# untitled.net
KiCad netlist of a schematic drawn in EAGLE
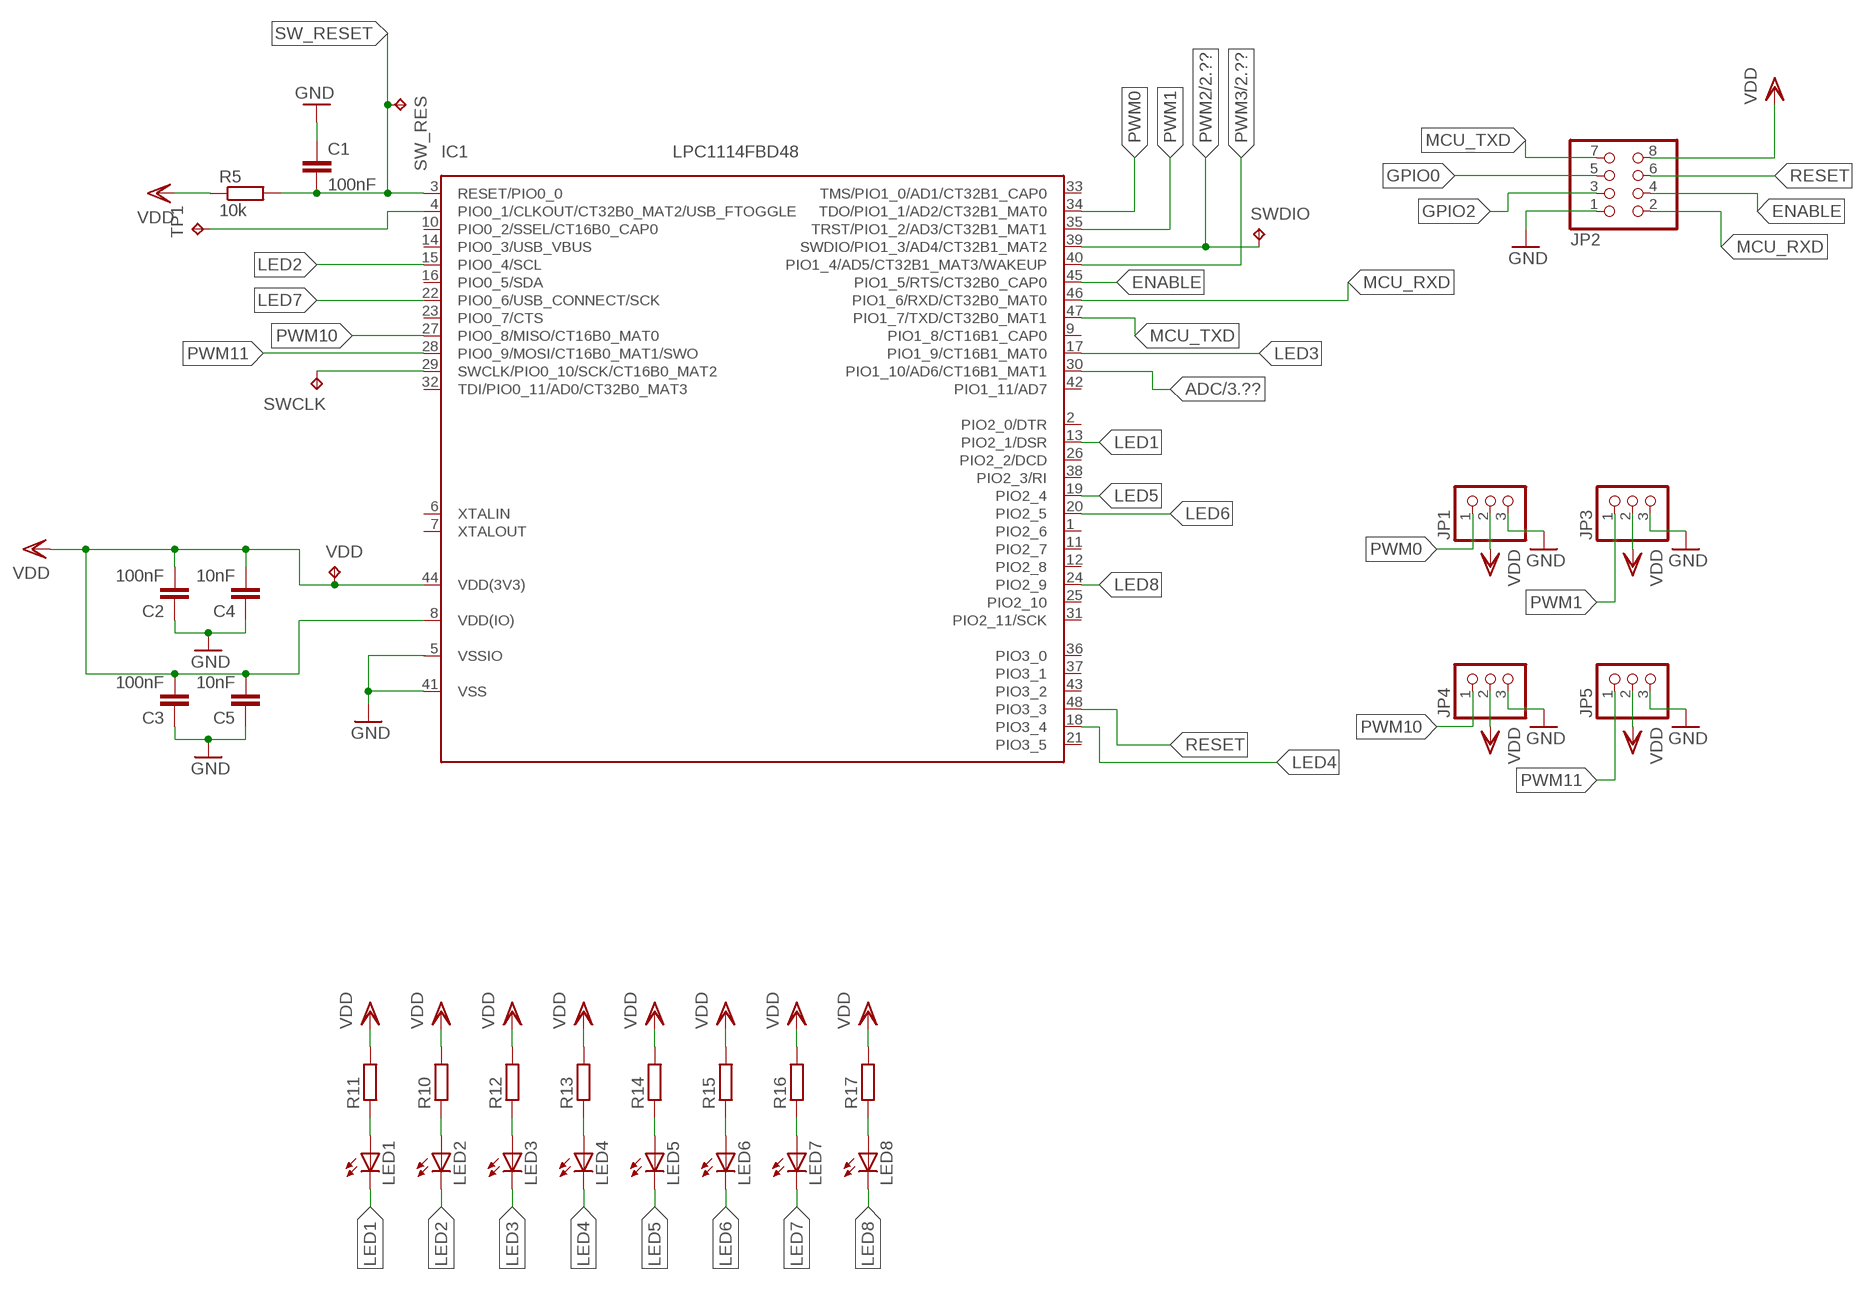
[diagram p0: schematic, sheet 1]
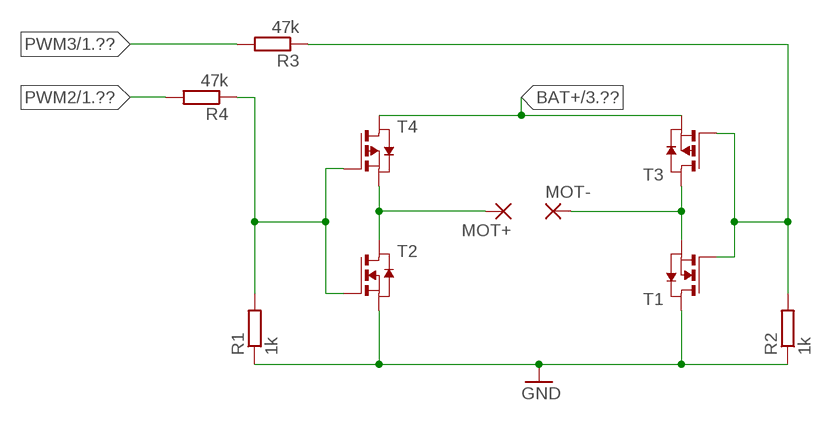
[diagram p1: schematic, sheet 2]
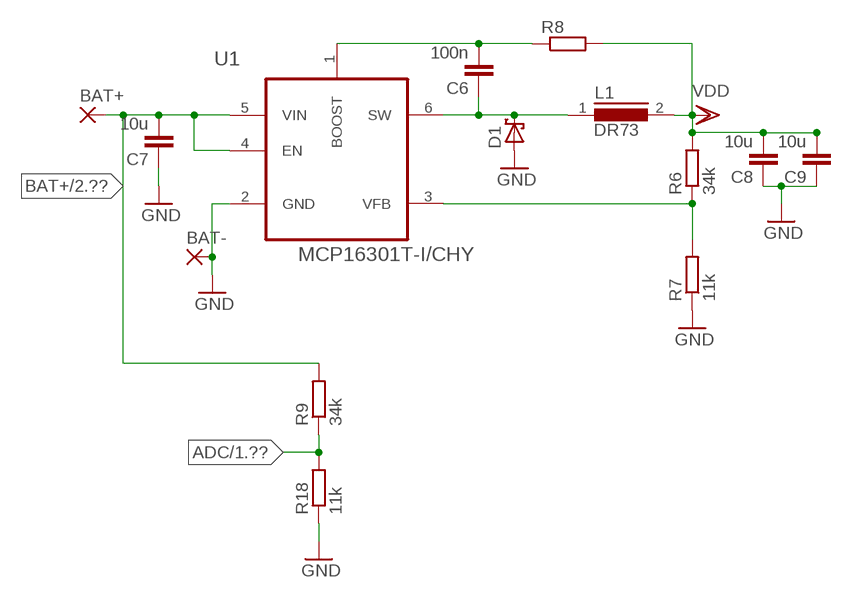
[diagram p2: schematic, sheet 3]

(export (version "E")
  (design (tool "Eeschema 10.0.6"))
  (components
    (comp (ref "MOT+")
      (value "SMD5")
      (footprint "eagle-import:SMD2,54-5,08")
      (libsource (lib "eagle-import") (part "SMD5"))
    )
    (comp (ref "MOT-")
      (value "SMD5")
      (footprint "eagle-import:SMD2,54-5,08")
      (libsource (lib "eagle-import") (part "SMD5"))
    )
    (comp (ref "R1")
      (value "1k")
      (footprint "eagle-import:R0805")
      (libsource (lib "eagle-import") (part "R-EU_R0805"))
    )
    (comp (ref "R2")
      (value "1k")
      (footprint "eagle-import:R0805")
      (libsource (lib "eagle-import") (part "R-EU_R0805"))
    )
    (comp (ref "R3")
      (value "47k")
      (footprint "eagle-import:R0805")
      (libsource (lib "eagle-import") (part "R-EU_R0805"))
    )
    (comp (ref "R4")
      (value "47k")
      (footprint "eagle-import:R0805")
      (libsource (lib "eagle-import") (part "R-EU_R0805"))
    )
    (comp (ref "T1")
      (value "NMOSSOT23")
      (footprint "eagle-import:SOT-23")
      (libsource (lib "eagle-import") (part "NMOSSOT23"))
    )
    (comp (ref "T2")
      (value "NMOSSOT23")
      (footprint "eagle-import:SOT-23")
      (libsource (lib "eagle-import") (part "NMOSSOT23"))
    )
    (comp (ref "T3")
      (value "PMOSSOT23")
      (footprint "eagle-import:SOT-23")
      (libsource (lib "eagle-import") (part "PMOSSOT23"))
    )
    (comp (ref "T4")
      (value "PMOSSOT23")
      (footprint "eagle-import:SOT-23")
      (libsource (lib "eagle-import") (part "PMOSSOT23"))
    )
    (comp (ref "BAT+")
      (value "SMD5")
      (footprint "eagle-import:SMD2,54-5,08")
      (libsource (lib "eagle-import") (part "SMD5"))
    )
    (comp (ref "BAT-")
      (value "SMD5")
      (footprint "eagle-import:SMD2,54-5,08")
      (libsource (lib "eagle-import") (part "SMD5"))
    )
    (comp (ref "C6")
      (value "100n")
      (footprint "eagle-import:C0805")
      (libsource (lib "eagle-import") (part "C-EUC0805"))
    )
    (comp (ref "C7")
      (value "10u")
      (footprint "eagle-import:C0805")
      (libsource (lib "eagle-import") (part "C-EUC0805"))
    )
    (comp (ref "C8")
      (value "10u")
      (footprint "eagle-import:C0805")
      (libsource (lib "eagle-import") (part "C-EUC0805"))
    )
    (comp (ref "C9")
      (value "10u")
      (footprint "eagle-import:C0805")
      (libsource (lib "eagle-import") (part "C-EUC0805"))
    )
    (comp (ref "D1")
      (value "SCHOTTKY-DIODESMD")
      (footprint "eagle-import:SMB")
      (libsource (lib "eagle-import") (part "SCHOTTKY-DIODESMD"))
    )
    (comp (ref "L1")
      (value "DR73")
      (footprint "eagle-import:DR73")
      (libsource (lib "eagle-import") (part "DR73"))
    )
    (comp (ref "R6")
      (value "34k")
      (footprint "eagle-import:R0805")
      (libsource (lib "eagle-import") (part "R-EU_R0805"))
    )
    (comp (ref "R7")
      (value "11k")
      (footprint "eagle-import:R0805")
      (libsource (lib "eagle-import") (part "R-EU_R0805"))
    )
    (comp (ref "R8")
      (value "R-EU_R0603")
      (footprint "eagle-import:R0603")
      (libsource (lib "eagle-import") (part "R-EU_R0603"))
    )
    (comp (ref "R9")
      (value "34k")
      (footprint "eagle-import:R0805")
      (libsource (lib "eagle-import") (part "R-EU_R0805"))
    )
    (comp (ref "R18")
      (value "11k")
      (footprint "eagle-import:R0805")
      (libsource (lib "eagle-import") (part "R-EU_R0805"))
    )
    (comp (ref "U1")
      (value "MCP16301T-I/CHY")
      (footprint "eagle-import:SOT95P290X145-6N")
      (libsource (lib "eagle-import") (part "MCP16301T-I/CHY"))
    )
    (comp (ref "C1")
      (value "100nF")
      (footprint "eagle-import:C0805")
      (libsource (lib "eagle-import") (part "C-EUC0805"))
    )
    (comp (ref "C2")
      (value "100nF")
      (footprint "eagle-import:C0805")
      (libsource (lib "eagle-import") (part "C-EUC0805"))
    )
    (comp (ref "C3")
      (value "100nF")
      (footprint "eagle-import:C0805")
      (libsource (lib "eagle-import") (part "C-EUC0805"))
    )
    (comp (ref "C4")
      (value "10nF")
      (footprint "eagle-import:C0805")
      (libsource (lib "eagle-import") (part "C-EUC0805"))
    )
    (comp (ref "C5")
      (value "10nF")
      (footprint "eagle-import:C0805")
      (libsource (lib "eagle-import") (part "C-EUC0805"))
    )
    (comp (ref "IC1")
      (value "LPC1114FBD48")
      (footprint "eagle-import:LQFP48-7X7")
      (libsource (lib "eagle-import") (part "LPC1114FBD48"))
    )
    (comp (ref "JP1")
      (value "PINHD-1X3")
      (footprint "eagle-import:1X03")
      (libsource (lib "eagle-import") (part "PINHD-1X3"))
    )
    (comp (ref "JP2")
      (value "PINHD-2X4")
      (footprint "eagle-import:2X04")
      (libsource (lib "eagle-import") (part "PINHD-2X4"))
    )
    (comp (ref "JP3")
      (value "PINHD-1X3")
      (footprint "eagle-import:1X03")
      (libsource (lib "eagle-import") (part "PINHD-1X3"))
    )
    (comp (ref "JP4")
      (value "PINHD-1X3")
      (footprint "eagle-import:1X03")
      (libsource (lib "eagle-import") (part "PINHD-1X3"))
    )
    (comp (ref "JP5")
      (value "PINHD-1X3")
      (footprint "eagle-import:1X03")
      (libsource (lib "eagle-import") (part "PINHD-1X3"))
    )
    (comp (ref "LED1")
      (value "LEDCHIP-LED0805")
      (footprint "eagle-import:CHIP-LED0805")
      (libsource (lib "eagle-import") (part "LEDCHIP-LED0805"))
    )
    (comp (ref "LED2")
      (value "LEDCHIP-LED0805")
      (footprint "eagle-import:CHIP-LED0805")
      (libsource (lib "eagle-import") (part "LEDCHIP-LED0805"))
    )
    (comp (ref "LED3")
      (value "LEDCHIP-LED0805")
      (footprint "eagle-import:CHIP-LED0805")
      (libsource (lib "eagle-import") (part "LEDCHIP-LED0805"))
    )
    (comp (ref "LED4")
      (value "LEDCHIP-LED0805")
      (footprint "eagle-import:CHIP-LED0805")
      (libsource (lib "eagle-import") (part "LEDCHIP-LED0805"))
    )
    (comp (ref "LED5")
      (value "LEDCHIP-LED0805")
      (footprint "eagle-import:CHIP-LED0805")
      (libsource (lib "eagle-import") (part "LEDCHIP-LED0805"))
    )
    (comp (ref "LED6")
      (value "LEDCHIP-LED0805")
      (footprint "eagle-import:CHIP-LED0805")
      (libsource (lib "eagle-import") (part "LEDCHIP-LED0805"))
    )
    (comp (ref "LED7")
      (value "LEDCHIP-LED0805")
      (footprint "eagle-import:CHIP-LED0805")
      (libsource (lib "eagle-import") (part "LEDCHIP-LED0805"))
    )
    (comp (ref "LED8")
      (value "LEDCHIP-LED0805")
      (footprint "eagle-import:CHIP-LED0805")
      (libsource (lib "eagle-import") (part "LEDCHIP-LED0805"))
    )
    (comp (ref "R5")
      (value "10k")
      (footprint "eagle-import:R0805")
      (libsource (lib "eagle-import") (part "R-EU_R0805"))
    )
    (comp (ref "R10")
      (value "R-EU_R0805")
      (footprint "eagle-import:R0805")
      (libsource (lib "eagle-import") (part "R-EU_R0805"))
    )
    (comp (ref "R11")
      (value "R-EU_R0805")
      (footprint "eagle-import:R0805")
      (libsource (lib "eagle-import") (part "R-EU_R0805"))
    )
    (comp (ref "R12")
      (value "R-EU_R0805")
      (footprint "eagle-import:R0805")
      (libsource (lib "eagle-import") (part "R-EU_R0805"))
    )
    (comp (ref "R13")
      (value "R-EU_R0805")
      (footprint "eagle-import:R0805")
      (libsource (lib "eagle-import") (part "R-EU_R0805"))
    )
    (comp (ref "R14")
      (value "R-EU_R0805")
      (footprint "eagle-import:R0805")
      (libsource (lib "eagle-import") (part "R-EU_R0805"))
    )
    (comp (ref "R15")
      (value "R-EU_R0805")
      (footprint "eagle-import:R0805")
      (libsource (lib "eagle-import") (part "R-EU_R0805"))
    )
    (comp (ref "R16")
      (value "R-EU_R0805")
      (footprint "eagle-import:R0805")
      (libsource (lib "eagle-import") (part "R-EU_R0805"))
    )
    (comp (ref "R17")
      (value "R-EU_R0805")
      (footprint "eagle-import:R0805")
      (libsource (lib "eagle-import") (part "R-EU_R0805"))
    )
    (comp (ref "SWCLK")
      (value "TPB1,27")
      (footprint "eagle-import:B1,27")
      (libsource (lib "eagle-import") (part "TPB1,27"))
    )
    (comp (ref "SWDIO")
      (value "TPB1,27")
      (footprint "eagle-import:B1,27")
      (libsource (lib "eagle-import") (part "TPB1,27"))
    )
    (comp (ref "SW_RES")
      (value "TPB1,27")
      (footprint "eagle-import:B1,27")
      (libsource (lib "eagle-import") (part "TPB1,27"))
    )
    (comp (ref "TP1")
      (value "TPB1,27")
      (footprint "eagle-import:B1,27")
      (libsource (lib "eagle-import") (part "TPB1,27"))
    )
    (comp (ref "VDD")
      (value "TPB1,27")
      (footprint "eagle-import:B1,27")
      (libsource (lib "eagle-import") (part "TPB1,27"))
    )
  )
  (nets
    (net (code "1") (name "ADC") (class "Default")
      (node (ref "IC1") (pin "30") (pinfunction "PIO1_10/AD6/CT16B1_MAT1_30") (pintype "bidirectional"))
      (node (ref "R18") (pin "2") (pinfunction "2_2") (pintype "passive"))
      (node (ref "R9") (pin "1") (pinfunction "1_1") (pintype "passive"))
    )
    (net (code "2") (name "BAT+") (class "Default")
      (node (ref "BAT+") (pin "1") (pinfunction "P_1") (pintype "passive"))
      (node (ref "C7") (pin "2") (pinfunction "2_2") (pintype "passive"))
      (node (ref "R9") (pin "2") (pinfunction "2_2") (pintype "passive"))
      (node (ref "T3") (pin "2") (pinfunction "S_2") (pintype "passive"))
      (node (ref "T4") (pin "1") (pinfunction "D_1") (pintype "passive"))
      (node (ref "U1") (pin "4") (pinfunction "EN_4") (pintype "input"))
      (node (ref "U1") (pin "5") (pinfunction "VIN_5") (pintype "input"))
    )
    (net (code "3") (name "ENABLE") (class "Default")
      (node (ref "IC1") (pin "45") (pinfunction "PIO1_5/RTS/CT32B0_CAP0_45") (pintype "bidirectional"))
      (node (ref "JP2") (pin "4") (pinfunction "4_4") (pintype "passive"))
    )
    (net (code "4") (name "GND") (class "Default")
      (node (ref "BAT-") (pin "1") (pinfunction "P_1") (pintype "passive"))
      (node (ref "C1") (pin "1") (pinfunction "1_1") (pintype "passive"))
      (node (ref "C2") (pin "1") (pinfunction "1_1") (pintype "passive"))
      (node (ref "C3") (pin "1") (pinfunction "1_1") (pintype "passive"))
      (node (ref "C4") (pin "1") (pinfunction "1_1") (pintype "passive"))
      (node (ref "C5") (pin "1") (pinfunction "1_1") (pintype "passive"))
      (node (ref "C7") (pin "1") (pinfunction "1_1") (pintype "passive"))
      (node (ref "C8") (pin "1") (pinfunction "1_1") (pintype "passive"))
      (node (ref "C9") (pin "1") (pinfunction "1_1") (pintype "passive"))
      (node (ref "D1") (pin "A") (pinfunction "A_A") (pintype "passive"))
      (node (ref "IC1") (pin "41") (pinfunction "VSS_41") (pintype "power_in"))
      (node (ref "JP1") (pin "3") (pinfunction "3_3") (pintype "passive"))
      (node (ref "JP2") (pin "1") (pinfunction "1_1") (pintype "passive"))
      (node (ref "JP3") (pin "3") (pinfunction "3_3") (pintype "passive"))
      (node (ref "JP4") (pin "3") (pinfunction "3_3") (pintype "passive"))
      (node (ref "JP5") (pin "3") (pinfunction "3_3") (pintype "passive"))
      (node (ref "R1") (pin "1") (pinfunction "1_1") (pintype "passive"))
      (node (ref "R18") (pin "1") (pinfunction "1_1") (pintype "passive"))
      (node (ref "R2") (pin "1") (pinfunction "1_1") (pintype "passive"))
      (node (ref "R7") (pin "1") (pinfunction "1_1") (pintype "passive"))
      (node (ref "T1") (pin "1") (pinfunction "D_1") (pintype "passive"))
      (node (ref "T2") (pin "2") (pinfunction "S_2") (pintype "passive"))
      (node (ref "U1") (pin "2") (pinfunction "GND_2") (pintype "passive"))
    )
    (net (code "5") (name "GPIO0") (class "Default")
      (node (ref "JP2") (pin "5") (pinfunction "5_5") (pintype "passive"))
    )
    (net (code "6") (name "GPIO2") (class "Default")
      (node (ref "JP2") (pin "3") (pinfunction "3_3") (pintype "passive"))
    )
    (net (code "7") (name "LED1") (class "Default")
      (node (ref "IC1") (pin "13") (pinfunction "PIO2_1/DSR_13") (pintype "bidirectional"))
      (node (ref "LED1") (pin "C") (pinfunction "C_C") (pintype "passive"))
    )
    (net (code "8") (name "LED2") (class "Default")
      (node (ref "IC1") (pin "15") (pinfunction "PIO0_4/SCL_15") (pintype "bidirectional"))
      (node (ref "LED2") (pin "C") (pinfunction "C_C") (pintype "passive"))
    )
    (net (code "9") (name "LED3") (class "Default")
      (node (ref "IC1") (pin "17") (pinfunction "PIO1_9/CT16B1_MAT0_17") (pintype "bidirectional"))
      (node (ref "LED3") (pin "C") (pinfunction "C_C") (pintype "passive"))
    )
    (net (code "10") (name "LED4") (class "Default")
      (node (ref "IC1") (pin "18") (pinfunction "PIO3_4_18") (pintype "bidirectional"))
      (node (ref "LED4") (pin "C") (pinfunction "C_C") (pintype "passive"))
    )
    (net (code "11") (name "LED5") (class "Default")
      (node (ref "IC1") (pin "19") (pinfunction "PIO2_4_19") (pintype "bidirectional"))
      (node (ref "LED5") (pin "C") (pinfunction "C_C") (pintype "passive"))
    )
    (net (code "12") (name "LED6") (class "Default")
      (node (ref "IC1") (pin "20") (pinfunction "PIO2_5_20") (pintype "bidirectional"))
      (node (ref "LED6") (pin "C") (pinfunction "C_C") (pintype "passive"))
    )
    (net (code "13") (name "LED7") (class "Default")
      (node (ref "IC1") (pin "22") (pinfunction "PIO0_6/USB_CONNECT/SCK_22") (pintype "bidirectional"))
      (node (ref "LED7") (pin "C") (pinfunction "C_C") (pintype "passive"))
    )
    (net (code "14") (name "LED8") (class "Default")
      (node (ref "IC1") (pin "24") (pinfunction "PIO2_9_24") (pintype "bidirectional"))
      (node (ref "LED8") (pin "C") (pinfunction "C_C") (pintype "passive"))
    )
    (net (code "15") (name "MCU_RXD") (class "Default")
      (node (ref "IC1") (pin "46") (pinfunction "PIO1_6/RXD/CT32B0_MAT0_46") (pintype "bidirectional"))
      (node (ref "JP2") (pin "2") (pinfunction "2_2") (pintype "passive"))
    )
    (net (code "16") (name "MCU_TXD") (class "Default")
      (node (ref "IC1") (pin "47") (pinfunction "PIO1_7/TXD/CT32B0_MAT1_47") (pintype "bidirectional"))
      (node (ref "JP2") (pin "7") (pinfunction "7_7") (pintype "passive"))
    )
    (net (code "17") (name "Net-(IC1-PIO0_1{slash}CLKOUT{slash}CT32B0_MAT2{slash}USB_FTOGGLE)") (class "Default")
      (node (ref "IC1") (pin "4") (pinfunction "PIO0_1/CLKOUT/CT32B0_MAT2/USB_FTOGGLE_4") (pintype "bidirectional"))
      (node (ref "TP1") (pin "TP") (pinfunction "TP_TP") (pintype "input"))
    )
    (net (code "18") (name "Net-(IC1-SWCLK{slash}PIO0_10{slash}SCK{slash}CT16B0_MAT2)") (class "Default")
      (node (ref "IC1") (pin "29") (pinfunction "SWCLK/PIO0_10/SCK/CT16B0_MAT2_29") (pintype "bidirectional"))
      (node (ref "SWCLK") (pin "TP") (pinfunction "TP_TP") (pintype "input"))
    )
    (net (code "19") (name "Net-(LED1-PadA)") (class "Default")
      (node (ref "LED1") (pin "A") (pinfunction "A_A") (pintype "passive"))
      (node (ref "R11") (pin "1") (pinfunction "1_1") (pintype "passive"))
    )
    (net (code "20") (name "Net-(LED2-PadA)") (class "Default")
      (node (ref "LED2") (pin "A") (pinfunction "A_A") (pintype "passive"))
      (node (ref "R10") (pin "1") (pinfunction "1_1") (pintype "passive"))
    )
    (net (code "21") (name "Net-(LED3-PadA)") (class "Default")
      (node (ref "LED3") (pin "A") (pinfunction "A_A") (pintype "passive"))
      (node (ref "R12") (pin "1") (pinfunction "1_1") (pintype "passive"))
    )
    (net (code "22") (name "Net-(LED4-PadA)") (class "Default")
      (node (ref "LED4") (pin "A") (pinfunction "A_A") (pintype "passive"))
      (node (ref "R13") (pin "1") (pinfunction "1_1") (pintype "passive"))
    )
    (net (code "23") (name "Net-(LED5-PadA)") (class "Default")
      (node (ref "LED5") (pin "A") (pinfunction "A_A") (pintype "passive"))
      (node (ref "R14") (pin "1") (pinfunction "1_1") (pintype "passive"))
    )
    (net (code "24") (name "Net-(LED6-PadA)") (class "Default")
      (node (ref "LED6") (pin "A") (pinfunction "A_A") (pintype "passive"))
      (node (ref "R15") (pin "1") (pinfunction "1_1") (pintype "passive"))
    )
    (net (code "25") (name "Net-(LED7-PadA)") (class "Default")
      (node (ref "LED7") (pin "A") (pinfunction "A_A") (pintype "passive"))
      (node (ref "R16") (pin "1") (pinfunction "1_1") (pintype "passive"))
    )
    (net (code "26") (name "Net-(LED8-PadA)") (class "Default")
      (node (ref "LED8") (pin "A") (pinfunction "A_A") (pintype "passive"))
      (node (ref "R17") (pin "1") (pinfunction "1_1") (pintype "passive"))
    )
    (net (code "27") (name "Net-(MOT+-P)") (class "Default")
      (node (ref "MOT+") (pin "1") (pinfunction "P_1") (pintype "passive"))
      (node (ref "T2") (pin "1") (pinfunction "D_1") (pintype "passive"))
      (node (ref "T4") (pin "2") (pinfunction "S_2") (pintype "passive"))
    )
    (net (code "28") (name "Net-(MOT--P)") (class "Default")
      (node (ref "MOT-") (pin "1") (pinfunction "P_1") (pintype "passive"))
      (node (ref "T1") (pin "2") (pinfunction "S_2") (pintype "passive"))
      (node (ref "T3") (pin "1") (pinfunction "D_1") (pintype "passive"))
    )
    (net (code "29") (name "Net-(T1-G)") (class "Default")
      (node (ref "R2") (pin "2") (pinfunction "2_2") (pintype "passive"))
      (node (ref "R3") (pin "1") (pinfunction "1_1") (pintype "passive"))
      (node (ref "T1") (pin "3") (pinfunction "G_3") (pintype "passive"))
      (node (ref "T3") (pin "3") (pinfunction "G_3") (pintype "passive"))
    )
    (net (code "30") (name "Net-(T2-G)") (class "Default")
      (node (ref "R1") (pin "2") (pinfunction "2_2") (pintype "passive"))
      (node (ref "R4") (pin "1") (pinfunction "1_1") (pintype "passive"))
      (node (ref "T2") (pin "3") (pinfunction "G_3") (pintype "passive"))
      (node (ref "T4") (pin "3") (pinfunction "G_3") (pintype "passive"))
    )
    (net (code "31") (name "Net-(U1-BOOST)") (class "Default")
      (node (ref "C6") (pin "2") (pinfunction "2_2") (pintype "passive"))
      (node (ref "R8") (pin "1") (pinfunction "1_1") (pintype "passive"))
      (node (ref "U1") (pin "1") (pinfunction "BOOST_1") (pintype "passive"))
    )
    (net (code "32") (name "Net-(U1-SW)") (class "Default")
      (node (ref "C6") (pin "1") (pinfunction "1_1") (pintype "passive"))
      (node (ref "D1") (pin "C") (pinfunction "C_C") (pintype "passive"))
      (node (ref "L1") (pin "1") (pinfunction "1_1") (pintype "passive"))
      (node (ref "U1") (pin "6") (pinfunction "SW_6") (pintype "output"))
    )
    (net (code "33") (name "Net-(U1-VFB)") (class "Default")
      (node (ref "R6") (pin "1") (pinfunction "1_1") (pintype "passive"))
      (node (ref "R7") (pin "2") (pinfunction "2_2") (pintype "passive"))
      (node (ref "U1") (pin "3") (pinfunction "VFB_3") (pintype "output"))
    )
    (net (code "34") (name "PWM0") (class "Default")
      (node (ref "IC1") (pin "34") (pinfunction "TDO/PIO1_1/AD2/CT32B1_MAT0_34") (pintype "bidirectional"))
      (node (ref "JP1") (pin "1") (pinfunction "1_1") (pintype "passive"))
    )
    (net (code "35") (name "PWM1") (class "Default")
      (node (ref "IC1") (pin "35") (pinfunction "TRST/PIO1_2/AD3/CT32B1_MAT1_35") (pintype "bidirectional"))
      (node (ref "JP3") (pin "1") (pinfunction "1_1") (pintype "passive"))
    )
    (net (code "36") (name "PWM2") (class "Default")
      (node (ref "IC1") (pin "39") (pinfunction "SWDIO/PIO1_3/AD4/CT32B1_MAT2_39") (pintype "bidirectional"))
      (node (ref "R4") (pin "2") (pinfunction "2_2") (pintype "passive"))
      (node (ref "SWDIO") (pin "TP") (pinfunction "TP_TP") (pintype "input"))
    )
    (net (code "37") (name "PWM3") (class "Default")
      (node (ref "IC1") (pin "40") (pinfunction "PIO1_4/AD5/CT32B1_MAT3/WAKEUP_40") (pintype "bidirectional"))
      (node (ref "R3") (pin "2") (pinfunction "2_2") (pintype "passive"))
    )
    (net (code "38") (name "PWM10") (class "Default")
      (node (ref "IC1") (pin "27") (pinfunction "PIO0_8/MISO/CT16B0_MAT0_27") (pintype "bidirectional"))
      (node (ref "JP4") (pin "1") (pinfunction "1_1") (pintype "passive"))
    )
    (net (code "39") (name "PWM11") (class "Default")
      (node (ref "IC1") (pin "28") (pinfunction "PIO0_9/MOSI/CT16B0_MAT1/SWO_28") (pintype "bidirectional"))
      (node (ref "JP5") (pin "1") (pinfunction "1_1") (pintype "passive"))
    )
    (net (code "40") (name "RESET") (class "Default")
      (node (ref "IC1") (pin "48") (pinfunction "PIO3_3_48") (pintype "bidirectional"))
      (node (ref "JP2") (pin "6") (pinfunction "6_6") (pintype "passive"))
    )
    (net (code "41") (name "SW_RESET") (class "Default")
      (node (ref "C1") (pin "2") (pinfunction "2_2") (pintype "passive"))
      (node (ref "IC1") (pin "3") (pinfunction "RESET/PIO0_0_3") (pintype "bidirectional"))
      (node (ref "R5") (pin "2") (pinfunction "2_2") (pintype "passive"))
      (node (ref "SW_RES") (pin "TP") (pinfunction "TP_TP") (pintype "input"))
    )
    (net (code "42") (name "VDD") (class "Default")
      (node (ref "C2") (pin "2") (pinfunction "2_2") (pintype "passive"))
      (node (ref "C3") (pin "2") (pinfunction "2_2") (pintype "passive"))
      (node (ref "C4") (pin "2") (pinfunction "2_2") (pintype "passive"))
      (node (ref "C5") (pin "2") (pinfunction "2_2") (pintype "passive"))
      (node (ref "C8") (pin "2") (pinfunction "2_2") (pintype "passive"))
      (node (ref "C9") (pin "2") (pinfunction "2_2") (pintype "passive"))
      (node (ref "IC1") (pin "44") (pinfunction "VDD(3V3)_44") (pintype "power_in"))
      (node (ref "IC1") (pin "8") (pinfunction "VDD(IO)_8") (pintype "power_in"))
      (node (ref "JP1") (pin "2") (pinfunction "2_2") (pintype "passive"))
      (node (ref "JP2") (pin "8") (pinfunction "8_8") (pintype "passive"))
      (node (ref "JP3") (pin "2") (pinfunction "2_2") (pintype "passive"))
      (node (ref "JP4") (pin "2") (pinfunction "2_2") (pintype "passive"))
      (node (ref "JP5") (pin "2") (pinfunction "2_2") (pintype "passive"))
      (node (ref "L1") (pin "2") (pinfunction "2_2") (pintype "passive"))
      (node (ref "R10") (pin "2") (pinfunction "2_2") (pintype "passive"))
      (node (ref "R11") (pin "2") (pinfunction "2_2") (pintype "passive"))
      (node (ref "R12") (pin "2") (pinfunction "2_2") (pintype "passive"))
      (node (ref "R13") (pin "2") (pinfunction "2_2") (pintype "passive"))
      (node (ref "R14") (pin "2") (pinfunction "2_2") (pintype "passive"))
      (node (ref "R15") (pin "2") (pinfunction "2_2") (pintype "passive"))
      (node (ref "R16") (pin "2") (pinfunction "2_2") (pintype "passive"))
      (node (ref "R17") (pin "2") (pinfunction "2_2") (pintype "passive"))
      (node (ref "R5") (pin "1") (pinfunction "1_1") (pintype "passive"))
      (node (ref "R6") (pin "2") (pinfunction "2_2") (pintype "passive"))
      (node (ref "R8") (pin "2") (pinfunction "2_2") (pintype "passive"))
      (node (ref "VDD") (pin "TP") (pinfunction "TP_TP") (pintype "input"))
    )
    (net (code "43") (name "VSSIO") (class "Default")
      (node (ref "IC1") (pin "5") (pinfunction "VSSIO_5") (pintype "power_in"))
    )
    (net (code "44") (name "unconnected-(IC1-PIO0_2{slash}SSEL{slash}CT16B0_CAP0-Pad10)") (class "Default")
      (node (ref "IC1") (pin "10") (pinfunction "PIO0_2/SSEL/CT16B0_CAP0_10") (pintype "bidirectional"))
    )
    (net (code "45") (name "unconnected-(IC1-PIO0_3{slash}USB_VBUS-Pad14)") (class "Default")
      (node (ref "IC1") (pin "14") (pinfunction "PIO0_3/USB_VBUS_14") (pintype "bidirectional"))
    )
    (net (code "46") (name "unconnected-(IC1-PIO0_5{slash}SDA-Pad16)") (class "Default")
      (node (ref "IC1") (pin "16") (pinfunction "PIO0_5/SDA_16") (pintype "bidirectional"))
    )
    (net (code "47") (name "unconnected-(IC1-PIO0_7{slash}CTS-Pad23)") (class "Default")
      (node (ref "IC1") (pin "23") (pinfunction "PIO0_7/CTS_23") (pintype "bidirectional"))
    )
    (net (code "48") (name "unconnected-(IC1-PIO1_8{slash}CT16B1_CAP0-Pad9)") (class "Default")
      (node (ref "IC1") (pin "9") (pinfunction "PIO1_8/CT16B1_CAP0_9") (pintype "bidirectional"))
    )
    (net (code "49") (name "unconnected-(IC1-PIO1_11{slash}AD7-Pad42)") (class "Default")
      (node (ref "IC1") (pin "42") (pinfunction "PIO1_11/AD7_42") (pintype "bidirectional"))
    )
    (net (code "50") (name "unconnected-(IC1-PIO2_0{slash}DTR-Pad2)") (class "Default")
      (node (ref "IC1") (pin "2") (pinfunction "PIO2_0/DTR_2") (pintype "bidirectional"))
    )
    (net (code "51") (name "unconnected-(IC1-PIO2_2{slash}DCD-Pad26)") (class "Default")
      (node (ref "IC1") (pin "26") (pinfunction "PIO2_2/DCD_26") (pintype "bidirectional"))
    )
    (net (code "52") (name "unconnected-(IC1-PIO2_3{slash}RI-Pad38)") (class "Default")
      (node (ref "IC1") (pin "38") (pinfunction "PIO2_3/RI_38") (pintype "bidirectional"))
    )
    (net (code "53") (name "unconnected-(IC1-PIO2_6-Pad1)") (class "Default")
      (node (ref "IC1") (pin "1") (pinfunction "PIO2_6_1") (pintype "bidirectional"))
    )
    (net (code "54") (name "unconnected-(IC1-PIO2_7-Pad11)") (class "Default")
      (node (ref "IC1") (pin "11") (pinfunction "PIO2_7_11") (pintype "bidirectional"))
    )
    (net (code "55") (name "unconnected-(IC1-PIO2_8-Pad12)") (class "Default")
      (node (ref "IC1") (pin "12") (pinfunction "PIO2_8_12") (pintype "bidirectional"))
    )
    (net (code "56") (name "unconnected-(IC1-PIO2_10-Pad25)") (class "Default")
      (node (ref "IC1") (pin "25") (pinfunction "PIO2_10_25") (pintype "bidirectional"))
    )
    (net (code "57") (name "unconnected-(IC1-PIO2_11{slash}SCK-Pad31)") (class "Default")
      (node (ref "IC1") (pin "31") (pinfunction "PIO2_11/SCK_31") (pintype "bidirectional"))
    )
    (net (code "58") (name "unconnected-(IC1-PIO3_0-Pad36)") (class "Default")
      (node (ref "IC1") (pin "36") (pinfunction "PIO3_0_36") (pintype "bidirectional"))
    )
    (net (code "59") (name "unconnected-(IC1-PIO3_1-Pad37)") (class "Default")
      (node (ref "IC1") (pin "37") (pinfunction "PIO3_1_37") (pintype "bidirectional"))
    )
    (net (code "60") (name "unconnected-(IC1-PIO3_2-Pad43)") (class "Default")
      (node (ref "IC1") (pin "43") (pinfunction "PIO3_2_43") (pintype "bidirectional"))
    )
    (net (code "61") (name "unconnected-(IC1-PIO3_5-Pad21)") (class "Default")
      (node (ref "IC1") (pin "21") (pinfunction "PIO3_5_21") (pintype "bidirectional"))
    )
    (net (code "62") (name "unconnected-(IC1-TDI{slash}PIO0_11{slash}AD0{slash}CT32B0_MAT3-Pad32)") (class "Default")
      (node (ref "IC1") (pin "32") (pinfunction "TDI/PIO0_11/AD0/CT32B0_MAT3_32") (pintype "bidirectional"))
    )
    (net (code "63") (name "unconnected-(IC1-TMS{slash}PIO1_0{slash}AD1{slash}CT32B1_CAP0-Pad33)") (class "Default")
      (node (ref "IC1") (pin "33") (pinfunction "TMS/PIO1_0/AD1/CT32B1_CAP0_33") (pintype "bidirectional"))
    )
    (net (code "64") (name "unconnected-(IC1-XTALIN-Pad6)") (class "Default")
      (node (ref "IC1") (pin "6") (pinfunction "XTALIN_6") (pintype "input"))
    )
    (net (code "65") (name "unconnected-(IC1-XTALOUT-Pad7)") (class "Default")
      (node (ref "IC1") (pin "7") (pinfunction "XTALOUT_7") (pintype "output"))
    )
  )
)
